# sch.net
KiCad netlist of a schematic drawn in Altium Designer
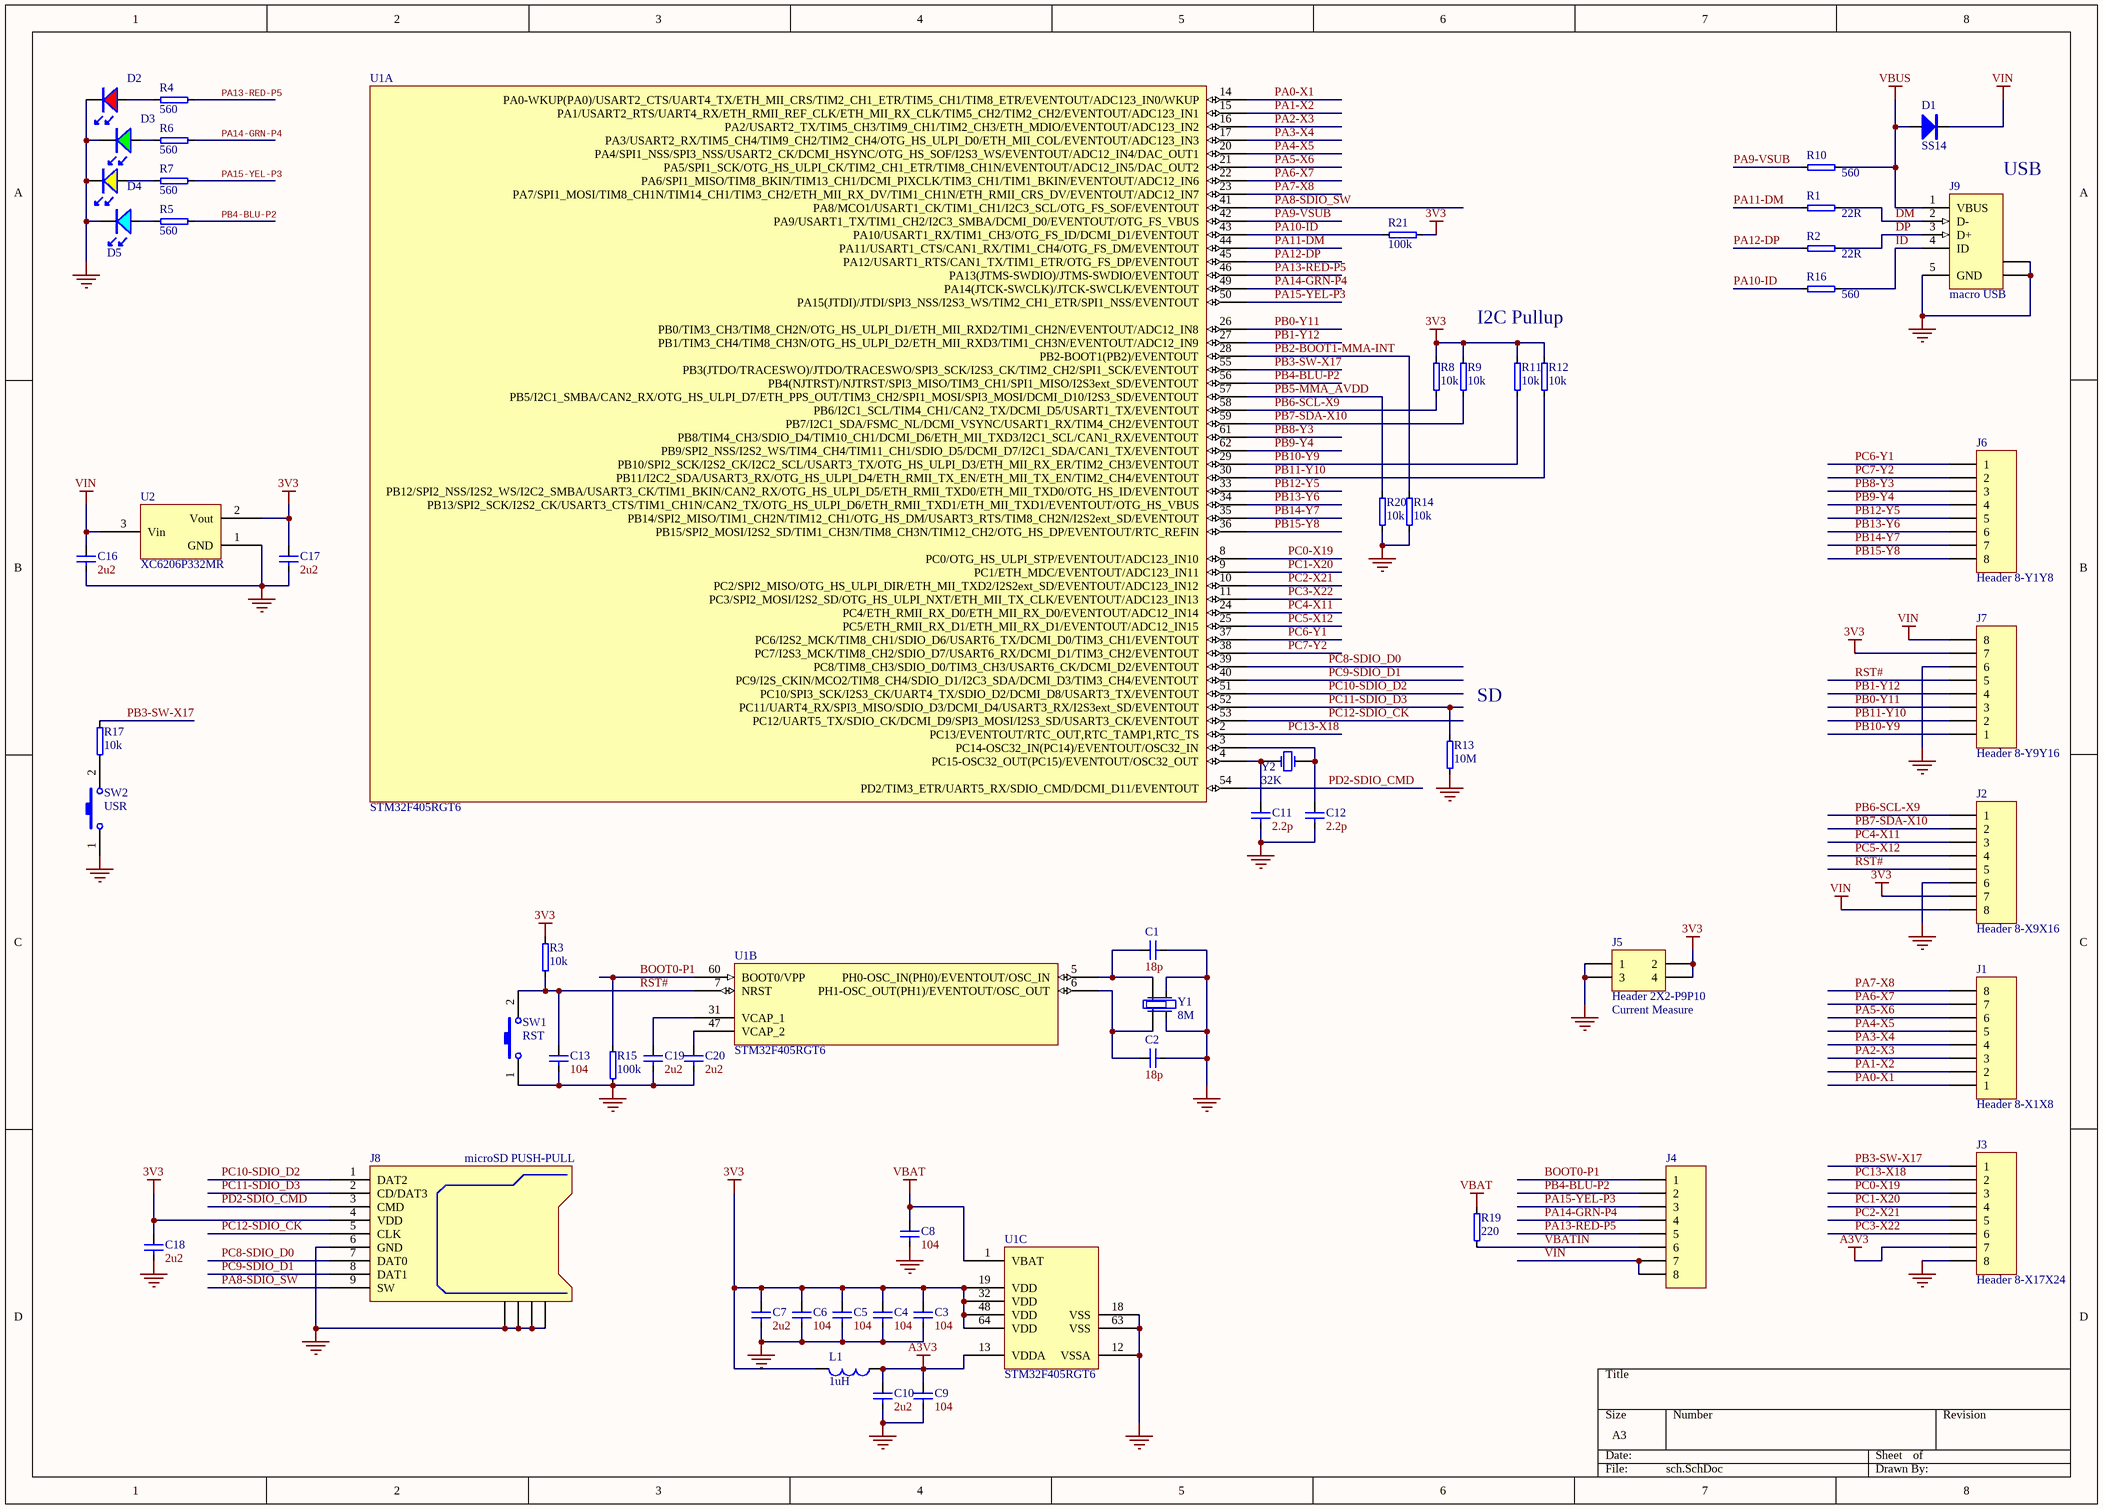
[diagram p0: sch.SchDoc]

(export (version "E")
  (design (tool "Eeschema 10.0.6"))
  (components
    (comp (ref "C1") (value "18p") (footprint "SMD0603") (libsource (lib "s_device") (part "Cap")))
    (comp (ref "C2") (value "18p") (footprint "SMD0603") (libsource (lib "s_device") (part "Cap")))
    (comp (ref "C3") (value "104") (footprint "SMD0603") (libsource (lib "s_device") (part "Cap")))
    (comp (ref "C4") (value "104") (footprint "SMD0603") (libsource (lib "s_device") (part "Cap")))
    (comp (ref "C5") (value "104") (footprint "SMD0603") (libsource (lib "s_device") (part "Cap")))
    (comp (ref "C6") (value "104") (footprint "SMD0603") (libsource (lib "s_device") (part "Cap")))
    (comp (ref "C7") (value "2u2") (footprint "SMD0805") (libsource (lib "s_device") (part "Cap")))
    (comp (ref "C8") (value "104") (footprint "SMD0603") (libsource (lib "s_device") (part "Cap")))
    (comp (ref "C9") (value "104") (footprint "SMD0603") (libsource (lib "s_device") (part "Cap")))
    (comp (ref "C10") (value "2u2") (footprint "SMD0805") (libsource (lib "s_device") (part "Cap")))
    (comp (ref "C11") (value "2.2p") (footprint "SMD0603") (libsource (lib "s_device") (part "Cap")))
    (comp (ref "C12") (value "2.2p") (footprint "SMD0603") (libsource (lib "s_device") (part "Cap")))
    (comp (ref "C13") (value "104") (footprint "SMD0603") (libsource (lib "s_device") (part "Cap")))
    (comp (ref "C16") (value "2u2") (footprint "SMD0805") (libsource (lib "s_device") (part "Cap")))
    (comp (ref "C17") (value "2u2") (footprint "SMD0805") (libsource (lib "s_device") (part "Cap")))
    (comp (ref "C18") (value "2u2") (footprint "SMD0805") (libsource (lib "s_device") (part "Cap")))
    (comp (ref "C19") (value "2u2") (footprint "SMD0805") (libsource (lib "s_device") (part "Cap")))
    (comp (ref "C20") (value "2u2") (footprint "SMD0805") (libsource (lib "s_device") (part "Cap")))
    (comp (ref "D1") (value "SS14") (footprint "SS24 - small") (libsource (lib "s_device") (part "Diode")))
    (comp (ref "D2")
      (value "LED RED")
      (footprint "LED0603")
      (description "红色发光二极管")
      (libsource (lib "s_device") (part "LED-RED"))
    )
    (comp (ref "D3")
      (value "LED GREEN")
      (footprint "LED0603")
      (description "绿色发光二极管")
      (libsource (lib "s_device") (part "LED-GREEN"))
    )
    (comp (ref "D4")
      (value "LED Yellow")
      (footprint "LED0603")
      (description "黄色发光二极管")
      (libsource (lib "s_device") (part "LED-YELLOW"))
    )
    (comp (ref "D5")
      (value "LED Blue")
      (footprint "LED0603")
      (description "蓝色发光二极管")
      (libsource (lib "s_device") (part "LED-BLUE"))
    )
    (comp (ref "J1")
      (value "Header 8-X1X8")
      (footprint "HDR1X8")
      (description "Header, 8-Pin")
      (fields (field (name "PUBLISHER") "Altium Limited"))
      (libsource (lib "Miscellaneous Connectors") (part "Header 8"))
    )
    (comp (ref "J2")
      (value "Header 8-X9X16")
      (footprint "HDR1X8")
      (description "Header, 8-Pin")
      (fields (field (name "PUBLISHER") "Altium Limited"))
      (libsource (lib "") (part "Header 8_1"))
    )
    (comp (ref "J3")
      (value "Header 8-X17X24")
      (footprint "HDR1X8")
      (description "Header, 8-Pin")
      (fields (field (name "PUBLISHER") "Altium Limited"))
      (libsource (lib "") (part "Header 8_1"))
    )
    (comp (ref "J4")
      (value "~")
      (footprint "HDR1X8")
      (description "Header, 8-Pin")
      (fields (field (name "PUBLISHER") "Altium Limited"))
      (libsource (lib "") (part "Header 8_1"))
    )
    (comp (ref "J5")
      (value "Header 2X2-P9P10")
      (footprint "HDR2X2")
      (description "Header, 2-Pin, Dual row")
      (fields (field (name "PUBLISHER") "Altium Limited"))
      (libsource (lib "Miscellaneous Connectors") (part "Header 2X2"))
    )
    (comp (ref "J6")
      (value "Header 8-Y1Y8")
      (footprint "HDR1X8")
      (description "Header, 8-Pin")
      (fields (field (name "PUBLISHER") "Altium Limited"))
      (libsource (lib "") (part "Header 8_1"))
    )
    (comp (ref "J7")
      (value "Header 8-Y9Y16")
      (footprint "HDR1X8")
      (description "Header, 8-Pin")
      (fields (field (name "PUBLISHER") "Altium Limited"))
      (libsource (lib "Miscellaneous Connectors") (part "Header 8"))
    )
    (comp (ref "J8")
      (value "microSD PUSH-PULL")
      (footprint "microSD-1")
      (libsource (lib "s_device") (part "microSD PUSH-PULL"))
    )
    (comp (ref "J9")
      (value "macro USB")
      (footprint "MicroUSB")
      (description "USB 2.0, Right Angle, SMT, B Type, Receptacle, 5 Position, Black")
      (fields (field (name "PUBLISHER") "Altium Limited"))
      (libsource (lib "s_connect") (part "macro USB"))
    )
    (comp (ref "L1")
      (value "1uH")
      (footprint "SMD0603")
      (fields (field (name "PUBLISHER") "Altium Limited"))
      (libsource (lib "s_device") (part "Inductor"))
    )
    (comp (ref "R1") (value "22R") (footprint "SMD0603") (libsource (lib "s_device") (part "Res")))
    (comp (ref "R2") (value "22R") (footprint "SMD0603") (libsource (lib "s_device") (part "Res")))
    (comp (ref "R3") (value "10k") (footprint "SMD0603") (libsource (lib "s_device") (part "Res")))
    (comp (ref "R4") (value "560") (footprint "SMD0603") (libsource (lib "s_device") (part "Res")))
    (comp (ref "R5") (value "560") (footprint "SMD0603") (libsource (lib "s_device") (part "Res")))
    (comp (ref "R6") (value "560") (footprint "SMD0603") (libsource (lib "s_device") (part "Res")))
    (comp (ref "R7") (value "560") (footprint "SMD0603") (libsource (lib "s_device") (part "Res")))
    (comp (ref "R8") (value "10k") (footprint "SMD0603") (libsource (lib "s_device") (part "Res")))
    (comp (ref "R9") (value "10k") (footprint "SMD0603") (libsource (lib "s_device") (part "Res")))
    (comp (ref "R10") (value "560") (footprint "SMD0603") (libsource (lib "s_device") (part "Res")))
    (comp (ref "R11") (value "10k") (footprint "SMD0603") (libsource (lib "s_device") (part "Res")))
    (comp (ref "R12") (value "10k") (footprint "SMD0603") (libsource (lib "s_device") (part "Res")))
    (comp (ref "R13") (value "10M") (footprint "SMD0603") (libsource (lib "s_device") (part "Res")))
    (comp (ref "R14") (value "10k") (footprint "SMD0603") (libsource (lib "s_device") (part "Res")))
    (comp (ref "R15") (value "100k") (footprint "SMD0603") (libsource (lib "s_device") (part "Res")))
    (comp (ref "R16") (value "560") (footprint "SMD0603") (libsource (lib "s_device") (part "Res")))
    (comp (ref "R17") (value "10k") (footprint "SMD0603") (libsource (lib "s_device") (part "Res")))
    (comp (ref "R19") (value "220") (footprint "SMD0603") (libsource (lib "s_device") (part "Res")))
    (comp (ref "R20") (value "10k") (footprint "SMD0603") (libsource (lib "s_device") (part "Res")))
    (comp (ref "R21") (value "100k") (footprint "SMD0603") (libsource (lib "s_device") (part "Res")))
    (comp (ref "SW1")
      (value "RST")
      (footprint "SW 3x6")
      (description "Switch")
      (fields (field (name "PUBLISHER") "Altium Limited"))
      (libsource (lib "s_device") (part "SW-PB"))
    )
    (comp (ref "SW2")
      (value "USR")
      (footprint "SW 3x6")
      (description "Switch")
      (fields (field (name "PUBLISHER") "Altium Limited"))
      (libsource (lib "s_device") (part "SW-PB"))
    )
    (comp (ref "U1")
      (value "STM32F405RGT6")
      (footprint "LQFP64_M")
      (libsource (lib "s_mcu") (part "STM32F405RGT6"))
    )
    (comp (ref "U2")
      (value "XC6206P332MR")
      (footprint "SOT-23_N")
      (libsource (lib "s_power") (part "XC6206"))
    )
    (comp (ref "Y1") (value "8M") (footprint "SMD5032") (libsource (lib "s_crystal") (part "XTAL_SMD")))
    (comp (ref "Y2") (value "32K") (footprint "TXC_9H03200019") (libsource (lib "s_crystal") (part "XTAL")))
  )
  (nets
    (net (code "1") (name "/BOOT0-P1") (class "Default")
      (node (ref "J4") (pin "1") (pinfunction "1_1") (pintype "passive"))
      (node (ref "R15") (pin "2") (pintype "passive"))
      (node (ref "U1") (pin "60") (pinfunction "BOOT0/VPP_60") (pintype "input"))
    )
    (net (code "2") (name "/DM") (class "Default")
      (node (ref "J9") (pin "2") (pinfunction "D-_2") (pintype "input"))
      (node (ref "R1") (pin "2") (pintype "passive"))
    )
    (net (code "3") (name "/DP") (class "Default")
      (node (ref "J9") (pin "3") (pinfunction "D+_3") (pintype "input"))
      (node (ref "R2") (pin "2") (pintype "passive"))
    )
    (net (code "4") (name "/ID") (class "Default")
      (node (ref "J9") (pin "4") (pinfunction "ID_4") (pintype "power_in"))
      (node (ref "R16") (pin "2") (pintype "passive"))
    )
    (net (code "5") (name "/PA0-X1") (class "Default")
      (node (ref "J1") (pin "1") (pinfunction "1_1") (pintype "passive"))
      (node (ref "U1") (pin "14") (pinfunction "PA0-WKUP(PA0)/USART2_CTS/UART4_TX/ETH_MII_CRS/TIM2_CH1_ETR/TIM5_CH1/TIM8_ETR/EVENTOUT/ADC123_IN0/WKUP_14") (pintype "bidirectional"))
    )
    (net (code "6") (name "/PA1-X2") (class "Default")
      (node (ref "J1") (pin "2") (pinfunction "2_2") (pintype "passive"))
      (node (ref "U1") (pin "15") (pinfunction "PA1/USART2_RTS/UART4_RX/ETH_RMII_REF_CLK/ETH_MII_RX_CLK/TIM5_CH2/TIM2_CH2/EVENTOUT/ADC123_IN1_15") (pintype "bidirectional"))
    )
    (net (code "7") (name "/PA2-X3") (class "Default")
      (node (ref "J1") (pin "3") (pinfunction "3_3") (pintype "passive"))
      (node (ref "U1") (pin "16") (pinfunction "PA2/USART2_TX/TIM5_CH3/TIM9_CH1/TIM2_CH3/ETH_MDIO/EVENTOUT/ADC123_IN2_16") (pintype "bidirectional"))
    )
    (net (code "8") (name "/PA3-X4") (class "Default")
      (node (ref "J1") (pin "4") (pinfunction "4_4") (pintype "passive"))
      (node (ref "U1") (pin "17") (pinfunction "PA3/USART2_RX/TIM5_CH4/TIM9_CH2/TIM2_CH4/OTG_HS_ULPI_D0/ETH_MII_COL/EVENTOUT/ADC123_IN3_17") (pintype "bidirectional"))
    )
    (net (code "9") (name "/PA4-X5") (class "Default")
      (node (ref "J1") (pin "5") (pinfunction "5_5") (pintype "passive"))
      (node (ref "U1") (pin "20") (pinfunction "PA4/SPI1_NSS/SPI3_NSS/USART2_CK/DCMI_HSYNC/OTG_HS_SOF/I2S3_WS/EVENTOUT/ADC12_IN4/DAC_OUT1_20") (pintype "bidirectional"))
    )
    (net (code "10") (name "/PA5-X6") (class "Default")
      (node (ref "J1") (pin "6") (pinfunction "6_6") (pintype "passive"))
      (node (ref "U1") (pin "21") (pinfunction "PA5/SPI1_SCK/OTG_HS_ULPI_CK/TIM2_CH1_ETR/TIM8_CH1N/EVENTOUT/ADC12_IN5/DAC_OUT2_21") (pintype "bidirectional"))
    )
    (net (code "11") (name "/PA6-X7") (class "Default")
      (node (ref "J1") (pin "7") (pinfunction "7_7") (pintype "passive"))
      (node (ref "U1") (pin "22") (pinfunction "PA6/SPI1_MISO/TIM8_BKIN/TIM13_CH1/DCMI_PIXCLK/TIM3_CH1/TIM1_BKIN/EVENTOUT/ADC12_IN6_22") (pintype "bidirectional"))
    )
    (net (code "12") (name "/PA7-X8") (class "Default")
      (node (ref "J1") (pin "8") (pinfunction "8_8") (pintype "passive"))
      (node (ref "U1") (pin "23") (pinfunction "PA7/SPI1_MOSI/TIM8_CH1N/TIM14_CH1/TIM3_CH2/ETH_MII_RX_DV/TIM1_CH1N/ETH_RMII_CRS_DV/EVENTOUT/ADC12_IN7_23") (pintype "bidirectional"))
    )
    (net (code "13") (name "/PA8-SDIO_SW") (class "Default")
      (node (ref "J8") (pin "9") (pinfunction "SW_9") (pintype "passive"))
      (node (ref "U1") (pin "41") (pinfunction "PA8/MCO1/USART1_CK/TIM1_CH1/I2C3_SCL/OTG_FS_SOF/EVENTOUT_41") (pintype "bidirectional"))
    )
    (net (code "14") (name "/PA9-VSUB") (class "Default")
      (node (ref "R10") (pin "1") (pintype "passive"))
      (node (ref "U1") (pin "42") (pinfunction "PA9/USART1_TX/TIM1_CH2/I2C3_SMBA/DCMI_D0/EVENTOUT/OTG_FS_VBUS_42") (pintype "bidirectional"))
    )
    (net (code "15") (name "/PA10-ID") (class "Default")
      (node (ref "R16") (pin "1") (pintype "passive"))
      (node (ref "R21") (pin "2") (pintype "passive"))
      (node (ref "U1") (pin "43") (pinfunction "PA10/USART1_RX/TIM1_CH3/OTG_FS_ID/DCMI_D1/EVENTOUT_43") (pintype "bidirectional"))
    )
    (net (code "16") (name "/PA11-DM") (class "Default")
      (node (ref "R1") (pin "1") (pintype "passive"))
      (node (ref "U1") (pin "44") (pinfunction "PA11/USART1_CTS/CAN1_RX/TIM1_CH4/OTG_FS_DM/EVENTOUT_44") (pintype "bidirectional"))
    )
    (net (code "17") (name "/PA12-DP") (class "Default")
      (node (ref "R2") (pin "1") (pintype "passive"))
      (node (ref "U1") (pin "45") (pinfunction "PA12/USART1_RTS/CAN1_TX/TIM1_ETR/OTG_FS_DP/EVENTOUT_45") (pintype "bidirectional"))
    )
    (net (code "18") (name "/PA13-RED-P5") (class "Default")
      (node (ref "J4") (pin "5") (pinfunction "5_5") (pintype "passive"))
      (node (ref "R4") (pin "1") (pintype "passive"))
      (node (ref "U1") (pin "46") (pinfunction "PA13(JTMS-SWDIO)/JTMS-SWDIO/EVENTOUT_46") (pintype "bidirectional"))
    )
    (net (code "19") (name "/PA14-GRN-P4") (class "Default")
      (node (ref "J4") (pin "4") (pinfunction "4_4") (pintype "passive"))
      (node (ref "R6") (pin "1") (pintype "passive"))
      (node (ref "U1") (pin "49") (pinfunction "PA14(JTCK-SWCLK)/JTCK-SWCLK/EVENTOUT_49") (pintype "bidirectional"))
    )
    (net (code "20") (name "/PA15-YEL-P3") (class "Default")
      (node (ref "J4") (pin "3") (pinfunction "3_3") (pintype "passive"))
      (node (ref "R7") (pin "1") (pintype "passive"))
      (node (ref "U1") (pin "50") (pinfunction "PA15(JTDI)/JTDI/SPI3_NSS/I2S3_WS/TIM2_CH1_ETR/SPI1_NSS/EVENTOUT_50") (pintype "bidirectional"))
    )
    (net (code "21") (name "/PB0-Y11") (class "Default")
      (node (ref "J7") (pin "3") (pinfunction "3_3") (pintype "passive"))
      (node (ref "U1") (pin "26") (pinfunction "PB0/TIM3_CH3/TIM8_CH2N/OTG_HS_ULPI_D1/ETH_MII_RXD2/TIM1_CH2N/EVENTOUT/ADC12_IN8_26") (pintype "bidirectional"))
    )
    (net (code "22") (name "/PB1-Y12") (class "Default")
      (node (ref "J7") (pin "4") (pinfunction "4_4") (pintype "passive"))
      (node (ref "U1") (pin "27") (pinfunction "PB1/TIM3_CH4/TIM8_CH3N/OTG_HS_ULPI_D2/ETH_MII_RXD3/TIM1_CH3N/EVENTOUT/ADC12_IN9_27") (pintype "bidirectional"))
    )
    (net (code "23") (name "/PB2-BOOT1-MMA-INT") (class "Default")
      (node (ref "R14") (pin "1") (pintype "passive"))
      (node (ref "U1") (pin "28") (pinfunction "PB2-BOOT1(PB2)/EVENTOUT_28") (pintype "bidirectional"))
    )
    (net (code "24") (name "/PB3-SW-X17") (class "Default")
      (node (ref "J3") (pin "1") (pinfunction "1_1") (pintype "passive"))
      (node (ref "R17") (pin "2") (pintype "passive"))
      (node (ref "U1") (pin "55") (pinfunction "PB3(JTDO/TRACESWO)/JTDO/TRACESWO/SPI3_SCK/I2S3_CK/TIM2_CH2/SPI1_SCK/EVENTOUT_55") (pintype "bidirectional"))
    )
    (net (code "25") (name "/PB4-BLU-P2") (class "Default")
      (node (ref "J4") (pin "2") (pinfunction "2_2") (pintype "passive"))
      (node (ref "R5") (pin "1") (pintype "passive"))
      (node (ref "U1") (pin "56") (pinfunction "PB4(NJTRST)/NJTRST/SPI3_MISO/TIM3_CH1/SPI1_MISO/I2S3ext_SD/EVENTOUT_56") (pintype "bidirectional"))
    )
    (net (code "26") (name "/PB5-MMA_AVDD") (class "Default")
      (node (ref "R20") (pin "1") (pintype "passive"))
      (node (ref "U1") (pin "57") (pinfunction "PB5/I2C1_SMBA/CAN2_RX/OTG_HS_ULPI_D7/ETH_PPS_OUT/TIM3_CH2/SPI1_MOSI/SPI3_MOSI/DCMI_D10/I2S3_SD/EVENTOUT_57") (pintype "bidirectional"))
    )
    (net (code "27") (name "/PB6-SCL-X9") (class "Default")
      (node (ref "J2") (pin "1") (pinfunction "1_1") (pintype "passive"))
      (node (ref "R8") (pin "2") (pintype "passive"))
      (node (ref "U1") (pin "58") (pinfunction "PB6/I2C1_SCL/TIM4_CH1/CAN2_TX/DCMI_D5/USART1_TX/EVENTOUT_58") (pintype "bidirectional"))
    )
    (net (code "28") (name "/PB7-SDA-X10") (class "Default")
      (node (ref "J2") (pin "2") (pinfunction "2_2") (pintype "passive"))
      (node (ref "R9") (pin "2") (pintype "passive"))
      (node (ref "U1") (pin "59") (pinfunction "PB7/I2C1_SDA/FSMC_NL/DCMI_VSYNC/USART1_RX/TIM4_CH2/EVENTOUT_59") (pintype "bidirectional"))
    )
    (net (code "29") (name "/PB8-Y3") (class "Default")
      (node (ref "J6") (pin "3") (pinfunction "3_3") (pintype "passive"))
      (node (ref "U1") (pin "61") (pinfunction "PB8/TIM4_CH3/SDIO_D4/TIM10_CH1/DCMI_D6/ETH_MII_TXD3/I2C1_SCL/CAN1_RX/EVENTOUT_61") (pintype "bidirectional"))
    )
    (net (code "30") (name "/PB9-Y4") (class "Default")
      (node (ref "J6") (pin "4") (pinfunction "4_4") (pintype "passive"))
      (node (ref "U1") (pin "62") (pinfunction "PB9/SPI2_NSS/I2S2_WS/TIM4_CH4/TIM11_CH1/SDIO_D5/DCMI_D7/I2C1_SDA/CAN1_TX/EVENTOUT_62") (pintype "bidirectional"))
    )
    (net (code "31") (name "/PB10-Y9") (class "Default")
      (node (ref "J7") (pin "1") (pinfunction "1_1") (pintype "passive"))
      (node (ref "R11") (pin "2") (pintype "passive"))
      (node (ref "U1") (pin "29") (pinfunction "PB10/SPI2_SCK/I2S2_CK/I2C2_SCL/USART3_TX/OTG_HS_ULPI_D3/ETH_MII_RX_ER/TIM2_CH3/EVENTOUT_29") (pintype "bidirectional"))
    )
    (net (code "32") (name "/PB11-Y10") (class "Default")
      (node (ref "J7") (pin "2") (pinfunction "2_2") (pintype "passive"))
      (node (ref "R12") (pin "2") (pintype "passive"))
      (node (ref "U1") (pin "30") (pinfunction "PB11/I2C2_SDA/USART3_RX/OTG_HS_ULPI_D4/ETH_RMII_TX_EN/ETH_MII_TX_EN/TIM2_CH4/EVENTOUT_30") (pintype "bidirectional"))
    )
    (net (code "33") (name "/PB12-Y5") (class "Default")
      (node (ref "J6") (pin "5") (pinfunction "5_5") (pintype "passive"))
      (node (ref "U1") (pin "33") (pinfunction "PB12/SPI2_NSS/I2S2_WS/I2C2_SMBA/USART3_CK/TIM1_BKIN/CAN2_RX/OTG_HS_ULPI_D5/ETH_RMII_TXD0/ETH_MII_TXD0/OTG_HS_ID/EVENTOUT_33") (pintype "bidirectional"))
    )
    (net (code "34") (name "/PB13-Y6") (class "Default")
      (node (ref "J6") (pin "6") (pinfunction "6_6") (pintype "passive"))
      (node (ref "U1") (pin "34") (pinfunction "PB13/SPI2_SCK/I2S2_CK/USART3_CTS/TIM1_CH1N/CAN2_TX/OTG_HS_ULPI_D6/ETH_RMII_TXD1/ETH_MII_TXD1/EVENTOUT/OTG_HS_VBUS_34") (pintype "bidirectional"))
    )
    (net (code "35") (name "/PB14-Y7") (class "Default")
      (node (ref "J6") (pin "7") (pinfunction "7_7") (pintype "passive"))
      (node (ref "U1") (pin "35") (pinfunction "PB14/SPI2_MISO/TIM1_CH2N/TIM12_CH1/OTG_HS_DM/USART3_RTS/TIM8_CH2N/I2S2ext_SD/EVENTOUT_35") (pintype "bidirectional"))
    )
    (net (code "36") (name "/PB15-Y8") (class "Default")
      (node (ref "J6") (pin "8") (pinfunction "8_8") (pintype "passive"))
      (node (ref "U1") (pin "36") (pinfunction "PB15/SPI2_MOSI/I2S2_SD/TIM1_CH3N/TIM8_CH3N/TIM12_CH2/OTG_HS_DP/EVENTOUT/RTC_REFIN_36") (pintype "bidirectional"))
    )
    (net (code "37") (name "/PC0-X19") (class "Default")
      (node (ref "J3") (pin "3") (pinfunction "3_3") (pintype "passive"))
      (node (ref "U1") (pin "8") (pinfunction "PC0/OTG_HS_ULPI_STP/EVENTOUT/ADC123_IN10_8") (pintype "bidirectional"))
    )
    (net (code "38") (name "/PC1-X20") (class "Default")
      (node (ref "J3") (pin "4") (pinfunction "4_4") (pintype "passive"))
      (node (ref "U1") (pin "9") (pinfunction "PC1/ETH_MDC/EVENTOUT/ADC123_IN11_9") (pintype "bidirectional"))
    )
    (net (code "39") (name "/PC2-X21") (class "Default")
      (node (ref "J3") (pin "5") (pinfunction "5_5") (pintype "passive"))
      (node (ref "U1") (pin "10") (pinfunction "PC2/SPI2_MISO/OTG_HS_ULPI_DIR/ETH_MII_TXD2/I2S2ext_SD/EVENTOUT/ADC123_IN12_10") (pintype "bidirectional"))
    )
    (net (code "40") (name "/PC3-X22") (class "Default")
      (node (ref "J3") (pin "6") (pinfunction "6_6") (pintype "passive"))
      (node (ref "U1") (pin "11") (pinfunction "PC3/SPI2_MOSI/I2S2_SD/OTG_HS_ULPI_NXT/ETH_MII_TX_CLK/EVENTOUT/ADC123_IN13_11") (pintype "bidirectional"))
    )
    (net (code "41") (name "/PC4-X11") (class "Default")
      (node (ref "J2") (pin "3") (pinfunction "3_3") (pintype "passive"))
      (node (ref "U1") (pin "24") (pinfunction "PC4/ETH_RMII_RX_D0/ETH_MII_RX_D0/EVENTOUT/ADC12_IN14_24") (pintype "bidirectional"))
    )
    (net (code "42") (name "/PC5-X12") (class "Default")
      (node (ref "J2") (pin "4") (pinfunction "4_4") (pintype "passive"))
      (node (ref "U1") (pin "25") (pinfunction "PC5/ETH_RMII_RX_D1/ETH_MII_RX_D1/EVENTOUT/ADC12_IN15_25") (pintype "bidirectional"))
    )
    (net (code "43") (name "/PC6-Y1") (class "Default")
      (node (ref "J6") (pin "1") (pinfunction "1_1") (pintype "passive"))
      (node (ref "U1") (pin "37") (pinfunction "PC6/I2S2_MCK/TIM8_CH1/SDIO_D6/USART6_TX/DCMI_D0/TIM3_CH1/EVENTOUT_37") (pintype "bidirectional"))
    )
    (net (code "44") (name "/PC7-Y2") (class "Default")
      (node (ref "J6") (pin "2") (pinfunction "2_2") (pintype "passive"))
      (node (ref "U1") (pin "38") (pinfunction "PC7/I2S3_MCK/TIM8_CH2/SDIO_D7/USART6_RX/DCMI_D1/TIM3_CH2/EVENTOUT_38") (pintype "bidirectional"))
    )
    (net (code "45") (name "/PC8-SDIO_D0") (class "Default")
      (node (ref "J8") (pin "7") (pinfunction "DAT0_7") (pintype "passive"))
      (node (ref "U1") (pin "39") (pinfunction "PC8/TIM8_CH3/SDIO_D0/TIM3_CH3/USART6_CK/DCMI_D2/EVENTOUT_39") (pintype "bidirectional"))
    )
    (net (code "46") (name "/PC9-SDIO_D1") (class "Default")
      (node (ref "J8") (pin "8") (pinfunction "DAT1_8") (pintype "passive"))
      (node (ref "U1") (pin "40") (pinfunction "PC9/I2S_CKIN/MCO2/TIM8_CH4/SDIO_D1/I2C3_SDA/DCMI_D3/TIM3_CH4/EVENTOUT_40") (pintype "bidirectional"))
    )
    (net (code "47") (name "/PC10-SDIO_D2") (class "Default")
      (node (ref "J8") (pin "1") (pinfunction "DAT2_1") (pintype "passive"))
      (node (ref "U1") (pin "51") (pinfunction "PC10/SPI3_SCK/I2S3_CK/UART4_TX/SDIO_D2/DCMI_D8/USART3_TX/EVENTOUT_51") (pintype "bidirectional"))
    )
    (net (code "48") (name "/PC11-SDIO_D3") (class "Default")
      (node (ref "J8") (pin "2") (pinfunction "CD/DAT3_2") (pintype "passive"))
      (node (ref "R13") (pin "1") (pintype "passive"))
      (node (ref "U1") (pin "52") (pinfunction "PC11/UART4_RX/SPI3_MISO/SDIO_D3/DCMI_D4/USART3_RX/I2S3ext_SD/EVENTOUT_52") (pintype "bidirectional"))
    )
    (net (code "49") (name "/PC12-SDIO_CK") (class "Default")
      (node (ref "J8") (pin "5") (pinfunction "CLK_5") (pintype "passive"))
      (node (ref "U1") (pin "53") (pinfunction "PC12/UART5_TX/SDIO_CK/DCMI_D9/SPI3_MOSI/I2S3_SD/USART3_CK/EVENTOUT_53") (pintype "bidirectional"))
    )
    (net (code "50") (name "/PC13-X18") (class "Default")
      (node (ref "J3") (pin "2") (pinfunction "2_2") (pintype "passive"))
      (node (ref "U1") (pin "2") (pinfunction "PC13/EVENTOUT/RTC_OUT,RTC_TAMP1,RTC_TS_2") (pintype "bidirectional"))
    )
    (net (code "51") (name "/PD2-SDIO_CMD") (class "Default")
      (node (ref "J8") (pin "3") (pinfunction "CMD_3") (pintype "passive"))
      (node (ref "U1") (pin "54") (pinfunction "PD2/TIM3_ETR/UART5_RX/SDIO_CMD/DCMI_D11/EVENTOUT_54") (pintype "bidirectional"))
    )
    (net (code "52") (name "/RST#") (class "Default")
      (node (ref "C13") (pin "2") (pintype "passive"))
      (node (ref "J2") (pin "5") (pinfunction "5_5") (pintype "passive"))
      (node (ref "J7") (pin "5") (pinfunction "5_5") (pintype "passive"))
      (node (ref "R3") (pin "1") (pintype "passive"))
      (node (ref "SW1") (pin "2") (pinfunction "2_2") (pintype "passive"))
      (node (ref "U1") (pin "7") (pinfunction "NRST_7") (pintype "bidirectional"))
    )
    (net (code "53") (name "/VBATIN") (class "Default")
      (node (ref "J4") (pin "6") (pinfunction "6_6") (pintype "passive"))
      (node (ref "R19") (pin "2") (pintype "passive"))
    )
    (net (code "54") (name "3V3") (class "Default")
      (node (ref "C17") (pin "2") (pintype "passive"))
      (node (ref "C18") (pin "2") (pintype "passive"))
      (node (ref "C3") (pin "2") (pintype "passive"))
      (node (ref "C4") (pin "2") (pintype "passive"))
      (node (ref "C5") (pin "2") (pintype "passive"))
      (node (ref "C6") (pin "2") (pintype "passive"))
      (node (ref "C7") (pin "2") (pintype "passive"))
      (node (ref "J2") (pin "7") (pinfunction "7_7") (pintype "passive"))
      (node (ref "J5") (pin "2") (pinfunction "2_2") (pintype "passive"))
      (node (ref "J5") (pin "4") (pinfunction "4_4") (pintype "passive"))
      (node (ref "J7") (pin "7") (pinfunction "7_7") (pintype "passive"))
      (node (ref "J8") (pin "4") (pinfunction "VDD_4") (pintype "passive"))
      (node (ref "L1") (pin "2") (pinfunction "2_2") (pintype "passive"))
      (node (ref "R11") (pin "1") (pintype "passive"))
      (node (ref "R12") (pin "1") (pintype "passive"))
      (node (ref "R21") (pin "1") (pintype "passive"))
      (node (ref "R3") (pin "2") (pintype "passive"))
      (node (ref "R8") (pin "1") (pintype "passive"))
      (node (ref "R9") (pin "1") (pintype "passive"))
      (node (ref "U1") (pin "19") (pinfunction "VDD_19") (pintype "power_in"))
      (node (ref "U1") (pin "32") (pinfunction "VDD_32") (pintype "power_in"))
      (node (ref "U1") (pin "48") (pinfunction "VDD_48") (pintype "power_in"))
      (node (ref "U1") (pin "64") (pinfunction "VDD_64") (pintype "power_in"))
      (node (ref "U2") (pin "2") (pinfunction "Vout_2") (pintype "passive"))
    )
    (net (code "55") (name "A3V3") (class "Default")
      (node (ref "C10") (pin "2") (pintype "passive"))
      (node (ref "C9") (pin "2") (pintype "passive"))
      (node (ref "J3") (pin "7") (pinfunction "7_7") (pintype "passive"))
      (node (ref "L1") (pin "1") (pinfunction "1_1") (pintype "passive"))
      (node (ref "U1") (pin "13") (pinfunction "VDDA_13") (pintype "power_in"))
    )
    (net (code "56") (name "GND") (class "Default")
      (node (ref "C1") (pin "1") (pintype "passive"))
      (node (ref "C10") (pin "1") (pintype "passive"))
      (node (ref "C11") (pin "1") (pintype "passive"))
      (node (ref "C12") (pin "1") (pintype "passive"))
      (node (ref "C13") (pin "1") (pintype "passive"))
      (node (ref "C16") (pin "1") (pintype "passive"))
      (node (ref "C17") (pin "1") (pintype "passive"))
      (node (ref "C18") (pin "1") (pintype "passive"))
      (node (ref "C19") (pin "1") (pintype "passive"))
      (node (ref "C2") (pin "1") (pintype "passive"))
      (node (ref "C20") (pin "1") (pintype "passive"))
      (node (ref "C3") (pin "1") (pintype "passive"))
      (node (ref "C4") (pin "1") (pintype "passive"))
      (node (ref "C5") (pin "1") (pintype "passive"))
      (node (ref "C6") (pin "1") (pintype "passive"))
      (node (ref "C7") (pin "1") (pintype "passive"))
      (node (ref "C8") (pin "1") (pintype "passive"))
      (node (ref "C9") (pin "1") (pintype "passive"))
      (node (ref "D2") (pin "2") (pintype "passive"))
      (node (ref "D3") (pin "2") (pintype "passive"))
      (node (ref "D4") (pin "2") (pintype "passive"))
      (node (ref "D5") (pin "2") (pintype "passive"))
      (node (ref "J2") (pin "6") (pinfunction "6_6") (pintype "passive"))
      (node (ref "J3") (pin "8") (pinfunction "8_8") (pintype "passive"))
      (node (ref "J5") (pin "1") (pinfunction "1_1") (pintype "passive"))
      (node (ref "J5") (pin "3") (pinfunction "3_3") (pintype "passive"))
      (node (ref "J7") (pin "6") (pinfunction "6_6") (pintype "passive"))
      (node (ref "J8") (pin "6") (pinfunction "GND_6") (pintype "passive"))
      (node (ref "J8") (pin "GP1") (pintype "passive"))
      (node (ref "J8") (pin "GP2") (pintype "passive"))
      (node (ref "J8") (pin "GP3") (pintype "passive"))
      (node (ref "J8") (pin "GP4") (pintype "passive"))
      (node (ref "J9") (pin "5") (pinfunction "GND_5") (pintype "passive"))
      (node (ref "J9") (pin "6") (pinfunction "SHLD_6") (pintype "passive"))
      (node (ref "J9") (pin "7") (pinfunction "SHLD_7") (pintype "passive"))
      (node (ref "R13") (pin "2") (pintype "passive"))
      (node (ref "R14") (pin "2") (pintype "passive"))
      (node (ref "R15") (pin "1") (pintype "passive"))
      (node (ref "R20") (pin "2") (pintype "passive"))
      (node (ref "SW1") (pin "1") (pinfunction "1_1") (pintype "passive"))
      (node (ref "SW2") (pin "1") (pinfunction "1_1") (pintype "passive"))
      (node (ref "U1") (pin "12") (pinfunction "VSSA_12") (pintype "power_in"))
      (node (ref "U1") (pin "18") (pinfunction "VSS_18") (pintype "power_in"))
      (node (ref "U1") (pin "63") (pinfunction "VSS_63") (pintype "power_in"))
      (node (ref "U2") (pin "1") (pinfunction "GND_1") (pintype "passive"))
      (node (ref "Y1") (pin "2") (pinfunction "GND_2") (pintype "passive"))
      (node (ref "Y1") (pin "4") (pinfunction "GND_4") (pintype "passive"))
    )
    (net (code "57") (name "Net-(D2-Pad1)") (class "Default")
      (node (ref "D2") (pin "1") (pintype "passive"))
      (node (ref "R4") (pin "2") (pintype "passive"))
    )
    (net (code "58") (name "Net-(D3-Pad1)") (class "Default")
      (node (ref "D3") (pin "1") (pintype "passive"))
      (node (ref "R6") (pin "2") (pintype "passive"))
    )
    (net (code "59") (name "Net-(D4-Pad1)") (class "Default")
      (node (ref "D4") (pin "1") (pintype "passive"))
      (node (ref "R7") (pin "2") (pintype "passive"))
    )
    (net (code "60") (name "Net-(D5-Pad1)") (class "Default")
      (node (ref "D5") (pin "1") (pintype "passive"))
      (node (ref "R5") (pin "2") (pintype "passive"))
    )
    (net (code "61") (name "Net-(R17-Pad1)") (class "Default")
      (node (ref "R17") (pin "1") (pintype "passive"))
      (node (ref "SW2") (pin "2") (pinfunction "2_2") (pintype "passive"))
    )
    (net (code "62") (name "Net-(U1A-PC14-OSC32_IN(PC14){slash}EVENTOUT{slash}OSC32_IN)") (class "Default")
      (node (ref "C12") (pin "2") (pintype "passive"))
      (node (ref "U1") (pin "3") (pinfunction "PC14-OSC32_IN(PC14)/EVENTOUT/OSC32_IN_3") (pintype "bidirectional"))
      (node (ref "Y2") (pin "2") (pinfunction "OSC2_2") (pintype "passive"))
    )
    (net (code "63") (name "Net-(U1A-PC15-OSC32_OUT(PC15){slash}EVENTOUT{slash}OSC32_OUT)") (class "Default")
      (node (ref "C11") (pin "2") (pintype "passive"))
      (node (ref "U1") (pin "4") (pinfunction "PC15-OSC32_OUT(PC15)/EVENTOUT/OSC32_OUT_4") (pintype "bidirectional"))
      (node (ref "Y2") (pin "1") (pinfunction "OSC1_1") (pintype "passive"))
    )
    (net (code "64") (name "Net-(U1B-PH0-OSC_IN(PH0){slash}EVENTOUT{slash}OSC_IN)") (class "Default")
      (node (ref "C1") (pin "2") (pintype "passive"))
      (node (ref "U1") (pin "5") (pinfunction "PH0-OSC_IN(PH0)/EVENTOUT/OSC_IN_5") (pintype "bidirectional"))
      (node (ref "Y1") (pin "3") (pinfunction "OSC2_3") (pintype "passive"))
    )
    (net (code "65") (name "Net-(U1B-PH1-OSC_OUT(PH1){slash}EVENTOUT{slash}OSC_OUT)") (class "Default")
      (node (ref "C2") (pin "2") (pintype "passive"))
      (node (ref "U1") (pin "6") (pinfunction "PH1-OSC_OUT(PH1)/EVENTOUT/OSC_OUT_6") (pintype "bidirectional"))
      (node (ref "Y1") (pin "1") (pinfunction "OSC1_1") (pintype "passive"))
    )
    (net (code "66") (name "Net-(U1B-VCAP_1)") (class "Default")
      (node (ref "C19") (pin "2") (pintype "passive"))
      (node (ref "U1") (pin "31") (pinfunction "VCAP_1_31") (pintype "power_in"))
    )
    (net (code "67") (name "Net-(U1B-VCAP_2)") (class "Default")
      (node (ref "C20") (pin "2") (pintype "passive"))
      (node (ref "U1") (pin "47") (pinfunction "VCAP_2_47") (pintype "power_in"))
    )
    (net (code "68") (name "VBAT") (class "Default")
      (node (ref "C8") (pin "2") (pintype "passive"))
      (node (ref "R19") (pin "1") (pintype "passive"))
      (node (ref "U1") (pin "1") (pinfunction "VBAT_1") (pintype "power_in"))
    )
    (net (code "69") (name "VBUS") (class "Default")
      (node (ref "D1") (pin "1") (pintype "passive"))
      (node (ref "J9") (pin "1") (pinfunction "VBUS_1") (pintype "power_in"))
      (node (ref "R10") (pin "2") (pintype "passive"))
    )
    (net (code "70") (name "VIN") (class "Default")
      (node (ref "C16") (pin "2") (pintype "passive"))
      (node (ref "D1") (pin "2") (pintype "passive"))
      (node (ref "J2") (pin "8") (pinfunction "8_8") (pintype "passive"))
      (node (ref "J4") (pin "7") (pinfunction "7_7") (pintype "passive"))
      (node (ref "J4") (pin "8") (pinfunction "8_8") (pintype "passive"))
      (node (ref "J7") (pin "8") (pinfunction "8_8") (pintype "passive"))
      (node (ref "U2") (pin "3") (pinfunction "Vin_3") (pintype "passive"))
    )
  )
)
